# SWR_VHF.net
KiCad netlist of a schematic drawn in Altium Designer
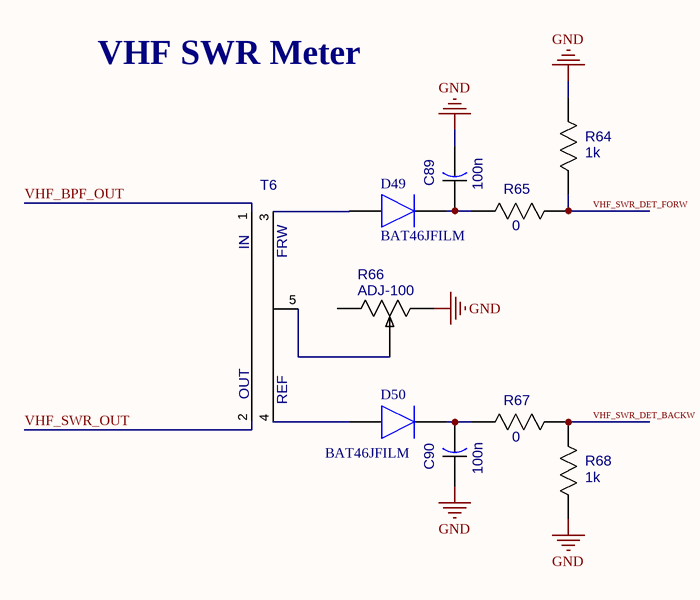
[diagram p0: SWR_VHF.SchDoc]

(export (version "E")
  (design (tool "Eeschema 10.0.6"))
  (components
    (comp (ref "C89")
      (value "100n")
      (footprint "CAP_0805")
      (description "CAP_0805")
      (libsource (lib "*") (part "CAP_0805"))
    )
    (comp (ref "C90")
      (value "100n")
      (footprint "CAP_0805")
      (description "CAP_0805")
      (libsource (lib "*") (part "CAP_0805"))
    )
    (comp (ref "D49")
      (value "BAT46JFILM")
      (footprint "SOD2513X117N")
      (description "Diode")
      (fields (field (name "MOUSER PART NUMBER") "511-BAT46JFILM") (field (name "RS PART NUMBER") "7146847P"))
      (libsource (lib "RF-UNIT-BIG") (part "BAT46JFILM"))
    )
    (comp (ref "D50")
      (value "BAT46JFILM")
      (footprint "SOD2513X117N")
      (description "Diode")
      (fields (field (name "MOUSER PART NUMBER") "511-BAT46JFILM") (field (name "RS PART NUMBER") "7146847P"))
      (libsource (lib "RF-UNIT-BIG") (part "BAT46JFILM"))
    )
    (comp (ref "R64")
      (value "1k")
      (footprint "RES_0805")
      (description "RES_0805")
      (libsource (lib "*") (part "RES_0805"))
    )
    (comp (ref "R65")
      (value "0")
      (footprint "RES_0805")
      (description "RES_0805")
      (libsource (lib "*") (part "RES_0805"))
    )
    (comp (ref "R66")
      (value "ADJ-100")
      (footprint "306J")
      (description "306J")
      (libsource (lib "*") (part "306J"))
    )
    (comp (ref "R67")
      (value "0")
      (footprint "RES_0805")
      (description "RES_0805")
      (libsource (lib "*") (part "RES_0805"))
    )
    (comp (ref "R68")
      (value "1k")
      (footprint "RES_0805")
      (description "RES_0805")
      (libsource (lib "*") (part "RES_0805"))
    )
    (comp (ref "T6") (value "SWR_VHF") (footprint "SWR_VHF") (libsource (lib "RF-UNIT-BIG") (part "SWR_VHF")))
  )
  (nets
    (net (code "1") (name "/VHF_BPF_OUT") (class "Default")
      (node (ref "T6") (pin "1") (pinfunction "1_1") (pintype "passive"))
    )
    (net (code "2") (name "/VHF_SWR_DET_BACKW") (class "Default")
      (node (ref "R67") (pin "2") (pinfunction "2_2") (pintype "passive"))
      (node (ref "R68") (pin "2") (pinfunction "2_2") (pintype "passive"))
    )
    (net (code "3") (name "/VHF_SWR_DET_FORW") (class "Default")
      (node (ref "R64") (pin "1") (pinfunction "1_1") (pintype "passive"))
      (node (ref "R65") (pin "2") (pinfunction "2_2") (pintype "passive"))
    )
    (net (code "4") (name "/VHF_SWR_OUT") (class "Default")
      (node (ref "T6") (pin "2") (pinfunction "2_2") (pintype "passive"))
    )
    (net (code "5") (name "GND") (class "Default")
      (node (ref "C89") (pin "2") (pinfunction "2_2") (pintype "passive"))
      (node (ref "C90") (pin "1") (pinfunction "1_1") (pintype "passive"))
      (node (ref "R64") (pin "2") (pinfunction "2_2") (pintype "passive"))
      (node (ref "R66") (pin "1") (pinfunction "CCW_1") (pintype "passive"))
      (node (ref "R68") (pin "1") (pinfunction "1_1") (pintype "passive"))
    )
    (net (code "6") (name "Net-(D49-A)") (class "Default")
      (node (ref "D49") (pin "2") (pinfunction "A_2") (pintype "passive"))
      (node (ref "T6") (pin "3") (pinfunction "3_3") (pintype "passive"))
    )
    (net (code "7") (name "Net-(D49-K)") (class "Default")
      (node (ref "C89") (pin "1") (pinfunction "1_1") (pintype "passive"))
      (node (ref "D49") (pin "1") (pinfunction "K_1") (pintype "passive"))
      (node (ref "R65") (pin "1") (pinfunction "1_1") (pintype "passive"))
    )
    (net (code "8") (name "Net-(D50-A)") (class "Default")
      (node (ref "D50") (pin "2") (pinfunction "A_2") (pintype "passive"))
      (node (ref "T6") (pin "4") (pinfunction "4_4") (pintype "passive"))
    )
    (net (code "9") (name "Net-(D50-K)") (class "Default")
      (node (ref "C90") (pin "2") (pinfunction "2_2") (pintype "passive"))
      (node (ref "D50") (pin "1") (pinfunction "K_1") (pintype "passive"))
      (node (ref "R67") (pin "1") (pinfunction "1_1") (pintype "passive"))
    )
    (net (code "10") (name "Net-(R66-W)") (class "Default")
      (node (ref "R66") (pin "2") (pinfunction "W_2") (pintype "passive"))
      (node (ref "T6") (pin "5") (pinfunction "5_5") (pintype "passive"))
    )
    (net (code "11") (name "unconnected-(R66-CW-Pad3)") (class "Default")
      (node (ref "R66") (pin "3") (pinfunction "CW_3") (pintype "passive"))
    )
  )
)
